# Sheet3.net
KiCad netlist of a schematic drawn in Altium Designer
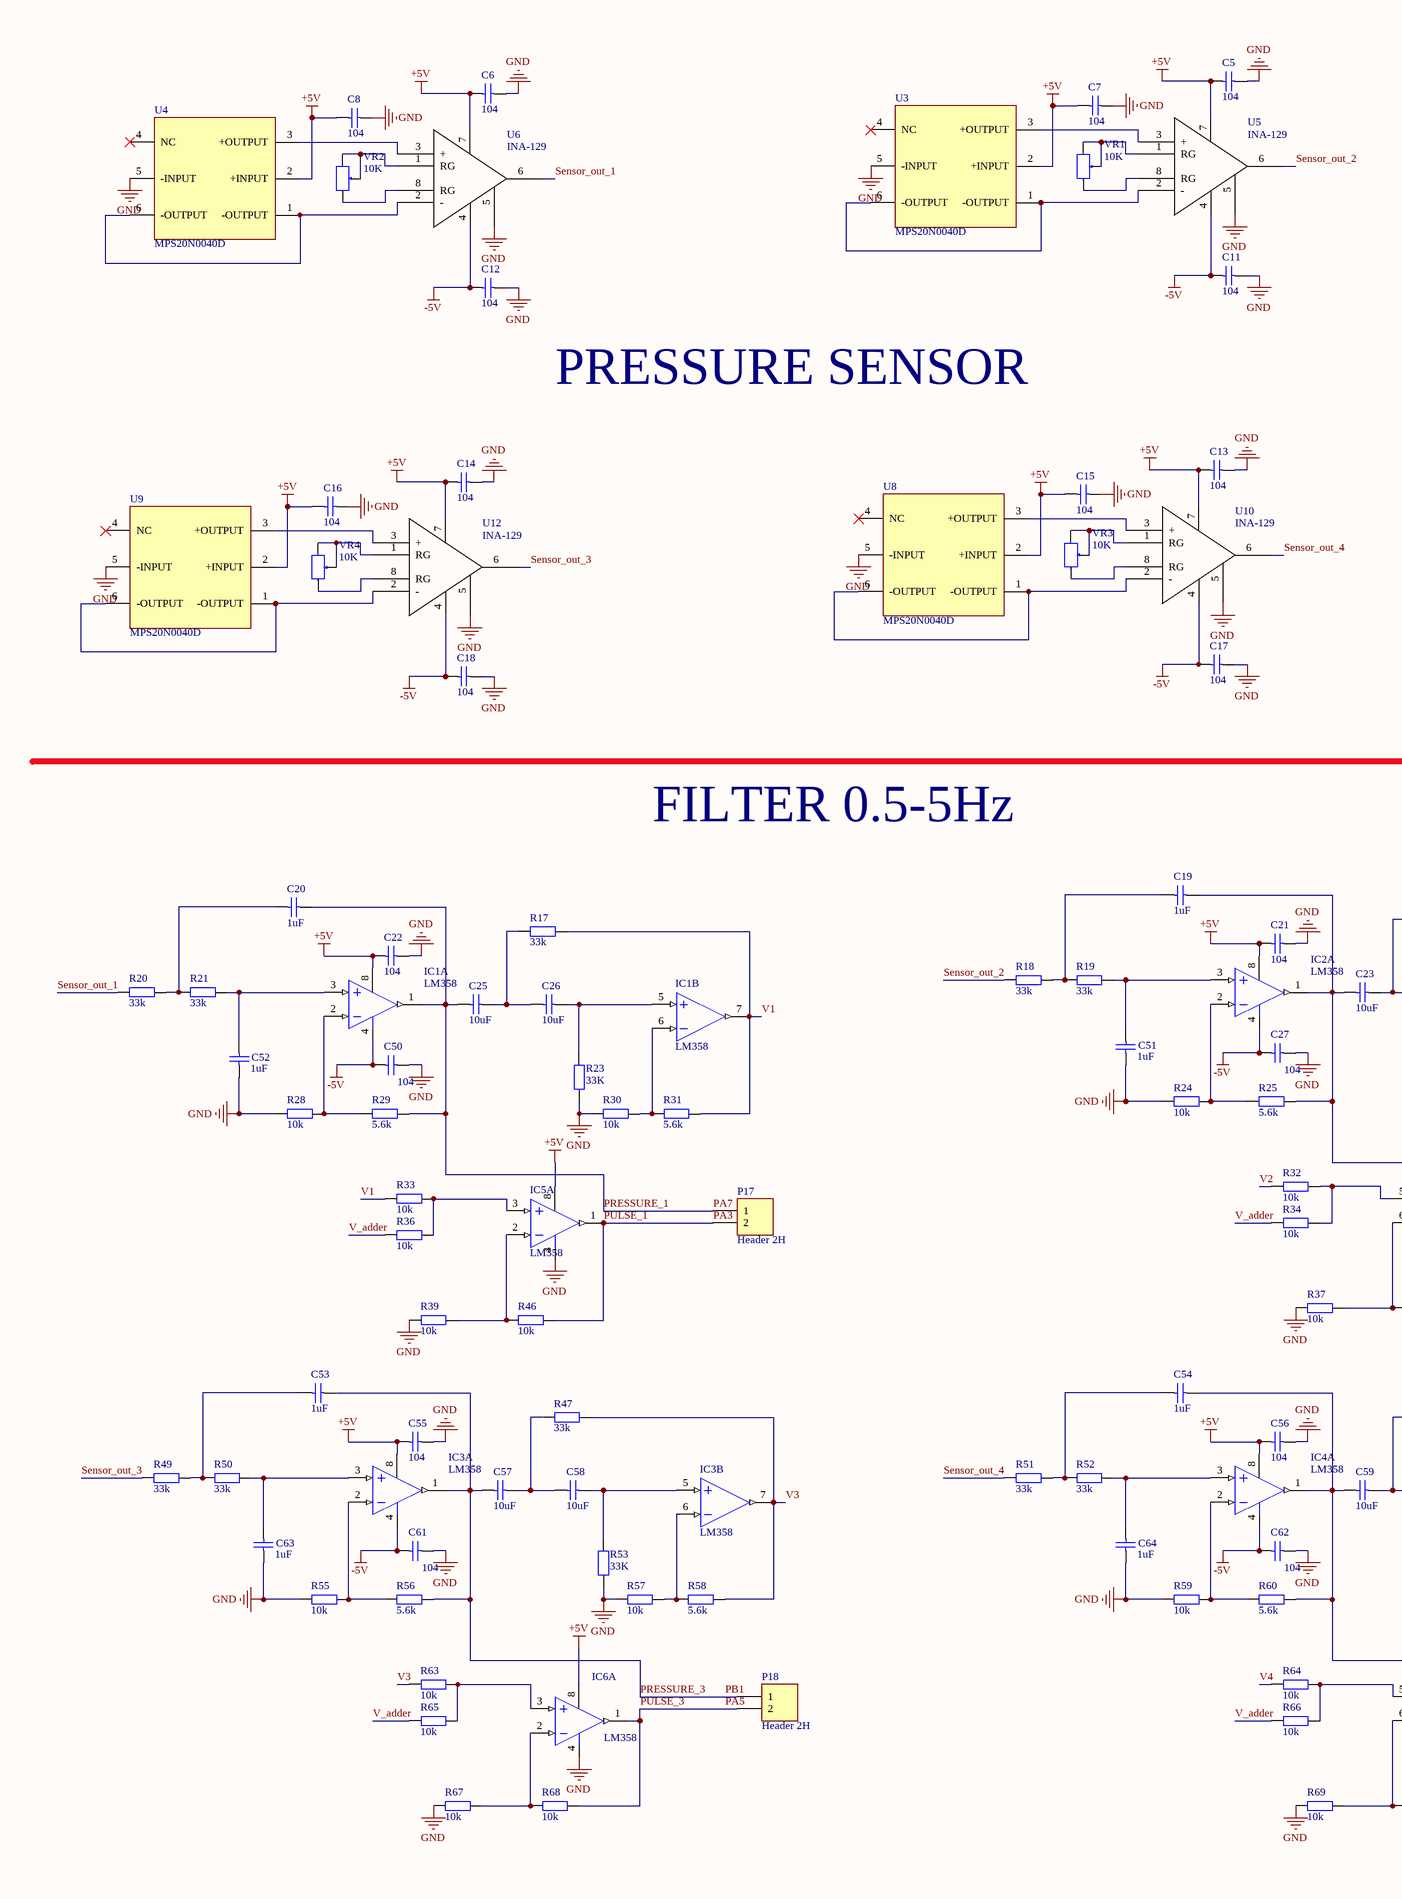
[diagram p0: Sheet3.SchDoc, left]
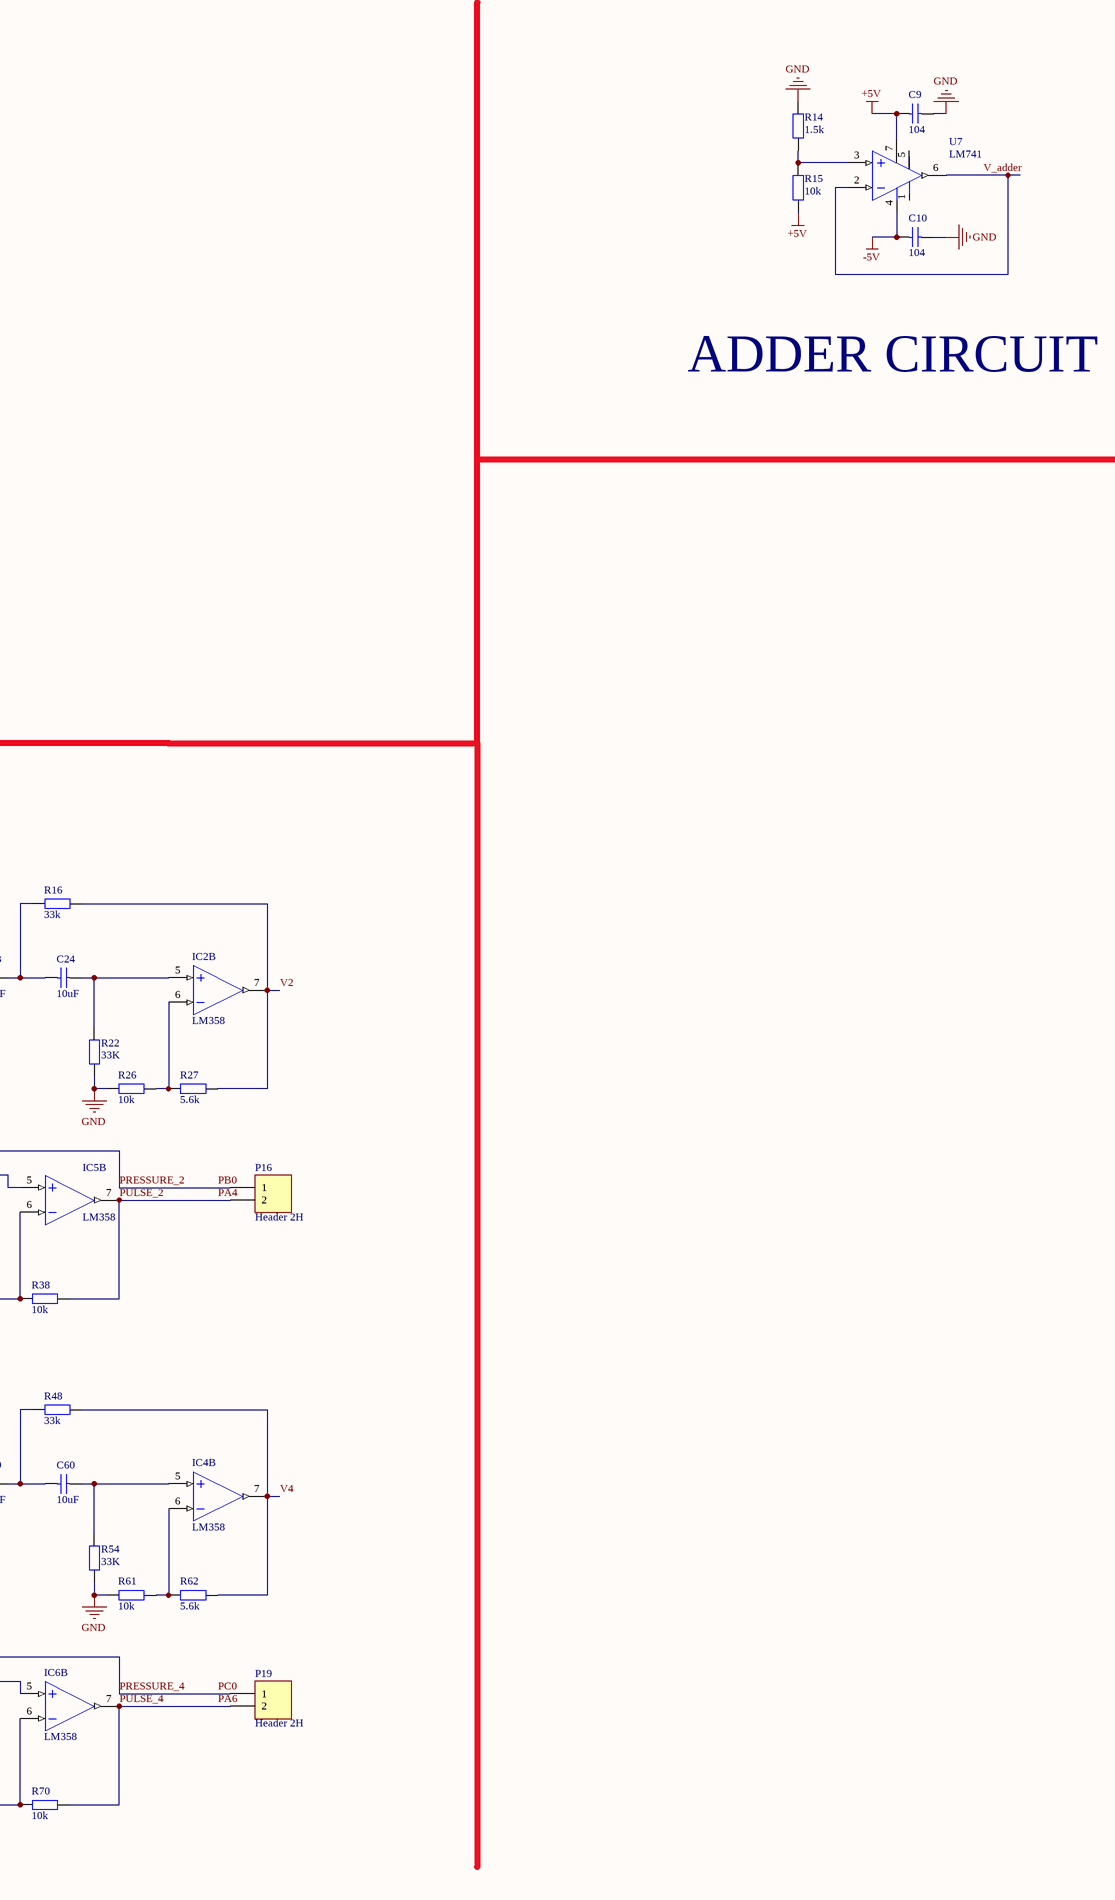
[diagram p1: Sheet3.SchDoc, right]

(export (version "E")
  (design (tool "Eeschema 10.0.6"))
  (components
    (comp (ref "C5")
      (value "104")
      (footprint "0805 CAP")
      (fields (field (name "PUBLISHER") "Altium Limited"))
      (libsource (lib "ThinhNguyenLib") (part "CAP CERAMIC"))
    )
    (comp (ref "C6")
      (value "104")
      (footprint "0805 CAP")
      (fields (field (name "PUBLISHER") "Altium Limited"))
      (libsource (lib "ThinhNguyenLib") (part "CAP CERAMIC"))
    )
    (comp (ref "C7")
      (value "104")
      (footprint "0805 CAP")
      (fields (field (name "PUBLISHER") "Altium Limited"))
      (libsource (lib "ThinhNguyenLib") (part "CAP CERAMIC"))
    )
    (comp (ref "C8")
      (value "104")
      (footprint "0805 CAP")
      (fields (field (name "PUBLISHER") "Altium Limited"))
      (libsource (lib "ThinhNguyenLib") (part "CAP CERAMIC"))
    )
    (comp (ref "C9")
      (value "104")
      (footprint "0805 CAP")
      (fields (field (name "PUBLISHER") "Altium Limited"))
      (libsource (lib "ThinhNguyenLib") (part "CAP CERAMIC"))
    )
    (comp (ref "C10")
      (value "104")
      (footprint "0805 CAP")
      (fields (field (name "PUBLISHER") "Altium Limited"))
      (libsource (lib "ThinhNguyenLib") (part "CAP CERAMIC"))
    )
    (comp (ref "C11")
      (value "104")
      (footprint "0805 CAP")
      (fields (field (name "PUBLISHER") "Altium Limited"))
      (libsource (lib "ThinhNguyenLib") (part "CAP CERAMIC"))
    )
    (comp (ref "C12")
      (value "104")
      (footprint "0805 CAP")
      (fields (field (name "PUBLISHER") "Altium Limited"))
      (libsource (lib "ThinhNguyenLib") (part "CAP CERAMIC"))
    )
    (comp (ref "C13")
      (value "104")
      (footprint "0805 CAP")
      (fields (field (name "PUBLISHER") "Altium Limited"))
      (libsource (lib "ThinhNguyenLib") (part "CAP CERAMIC"))
    )
    (comp (ref "C14")
      (value "104")
      (footprint "0805 CAP")
      (fields (field (name "PUBLISHER") "Altium Limited"))
      (libsource (lib "ThinhNguyenLib") (part "CAP CERAMIC"))
    )
    (comp (ref "C15")
      (value "104")
      (footprint "0805 CAP")
      (fields (field (name "PUBLISHER") "Altium Limited"))
      (libsource (lib "ThinhNguyenLib") (part "CAP CERAMIC"))
    )
    (comp (ref "C16")
      (value "104")
      (footprint "0805 CAP")
      (fields (field (name "PUBLISHER") "Altium Limited"))
      (libsource (lib "ThinhNguyenLib") (part "CAP CERAMIC"))
    )
    (comp (ref "C17")
      (value "104")
      (footprint "0805 CAP")
      (fields (field (name "PUBLISHER") "Altium Limited"))
      (libsource (lib "ThinhNguyenLib") (part "CAP CERAMIC"))
    )
    (comp (ref "C18")
      (value "104")
      (footprint "0805 CAP")
      (fields (field (name "PUBLISHER") "Altium Limited"))
      (libsource (lib "ThinhNguyenLib") (part "CAP CERAMIC"))
    )
    (comp (ref "C19")
      (value "1uF")
      (footprint "0805 CAP")
      (fields (field (name "PUBLISHER") "Altium Limited"))
      (libsource (lib "ThinhNguyenLib") (part "CAP CERAMIC"))
    )
    (comp (ref "C20")
      (value "1uF")
      (footprint "0805 CAP")
      (fields (field (name "PUBLISHER") "Altium Limited"))
      (libsource (lib "ThinhNguyenLib") (part "CAP CERAMIC"))
    )
    (comp (ref "C21")
      (value "104")
      (footprint "0805 CAP")
      (fields (field (name "PUBLISHER") "Altium Limited"))
      (libsource (lib "ThinhNguyenLib") (part "CAP CERAMIC"))
    )
    (comp (ref "C22")
      (value "104")
      (footprint "0805 CAP")
      (fields (field (name "PUBLISHER") "Altium Limited"))
      (libsource (lib "ThinhNguyenLib") (part "CAP CERAMIC"))
    )
    (comp (ref "C23")
      (value "10uF")
      (footprint "0805 CAP")
      (fields (field (name "PUBLISHER") "Altium Limited"))
      (libsource (lib "ThinhNguyenLib") (part "CAP CERAMIC"))
    )
    (comp (ref "C24")
      (value "10uF")
      (footprint "0805 CAP")
      (fields (field (name "PUBLISHER") "Altium Limited"))
      (libsource (lib "ThinhNguyenLib") (part "CAP CERAMIC"))
    )
    (comp (ref "C25")
      (value "10uF")
      (footprint "0805 CAP")
      (fields (field (name "PUBLISHER") "Altium Limited"))
      (libsource (lib "ThinhNguyenLib") (part "CAP CERAMIC"))
    )
    (comp (ref "C26")
      (value "10uF")
      (footprint "0805 CAP")
      (fields (field (name "PUBLISHER") "Altium Limited"))
      (libsource (lib "ThinhNguyenLib") (part "CAP CERAMIC"))
    )
    (comp (ref "C27")
      (value "104")
      (footprint "0805 CAP")
      (fields (field (name "PUBLISHER") "Altium Limited"))
      (libsource (lib "ThinhNguyenLib") (part "CAP CERAMIC"))
    )
    (comp (ref "C50")
      (value "104")
      (footprint "0805 CAP")
      (fields (field (name "PUBLISHER") "Altium Limited"))
      (libsource (lib "ThinhNguyenLib") (part "CAP CERAMIC"))
    )
    (comp (ref "C51")
      (value "1uF")
      (footprint "0805 CAP")
      (fields (field (name "PUBLISHER") "Altium Limited"))
      (libsource (lib "ThinhNguyenLib") (part "CAP CERAMIC"))
    )
    (comp (ref "C52")
      (value "1uF")
      (footprint "0805 CAP")
      (fields (field (name "PUBLISHER") "Altium Limited"))
      (libsource (lib "ThinhNguyenLib") (part "CAP CERAMIC"))
    )
    (comp (ref "C53")
      (value "1uF")
      (footprint "0805 CAP")
      (fields (field (name "PUBLISHER") "Altium Limited"))
      (libsource (lib "ThinhNguyenLib") (part "CAP CERAMIC"))
    )
    (comp (ref "C54")
      (value "1uF")
      (footprint "0805 CAP")
      (fields (field (name "PUBLISHER") "Altium Limited"))
      (libsource (lib "ThinhNguyenLib") (part "CAP CERAMIC"))
    )
    (comp (ref "C55")
      (value "104")
      (footprint "0805 CAP")
      (fields (field (name "PUBLISHER") "Altium Limited"))
      (libsource (lib "ThinhNguyenLib") (part "CAP CERAMIC"))
    )
    (comp (ref "C56")
      (value "104")
      (footprint "0805 CAP")
      (fields (field (name "PUBLISHER") "Altium Limited"))
      (libsource (lib "ThinhNguyenLib") (part "CAP CERAMIC"))
    )
    (comp (ref "C57")
      (value "10uF")
      (footprint "0805 CAP")
      (fields (field (name "PUBLISHER") "Altium Limited"))
      (libsource (lib "ThinhNguyenLib") (part "CAP CERAMIC"))
    )
    (comp (ref "C58")
      (value "10uF")
      (footprint "0805 CAP")
      (fields (field (name "PUBLISHER") "Altium Limited"))
      (libsource (lib "ThinhNguyenLib") (part "CAP CERAMIC"))
    )
    (comp (ref "C59")
      (value "10uF")
      (footprint "0805 CAP")
      (fields (field (name "PUBLISHER") "Altium Limited"))
      (libsource (lib "ThinhNguyenLib") (part "CAP CERAMIC"))
    )
    (comp (ref "C60")
      (value "10uF")
      (footprint "0805 CAP")
      (fields (field (name "PUBLISHER") "Altium Limited"))
      (libsource (lib "ThinhNguyenLib") (part "CAP CERAMIC"))
    )
    (comp (ref "C61")
      (value "104")
      (footprint "0805 CAP")
      (fields (field (name "PUBLISHER") "Altium Limited"))
      (libsource (lib "ThinhNguyenLib") (part "CAP CERAMIC"))
    )
    (comp (ref "C62")
      (value "104")
      (footprint "0805 CAP")
      (fields (field (name "PUBLISHER") "Altium Limited"))
      (libsource (lib "ThinhNguyenLib") (part "CAP CERAMIC"))
    )
    (comp (ref "C63")
      (value "1uF")
      (footprint "0805 CAP")
      (fields (field (name "PUBLISHER") "Altium Limited"))
      (libsource (lib "ThinhNguyenLib") (part "CAP CERAMIC"))
    )
    (comp (ref "C64")
      (value "1uF")
      (footprint "0805 CAP")
      (fields (field (name "PUBLISHER") "Altium Limited"))
      (libsource (lib "ThinhNguyenLib") (part "CAP CERAMIC"))
    )
    (comp (ref "IC1")
      (value "LM358")
      (footprint "SOIC 8PIN")
      (description "Low-Power Dual Operational Amplifier")
      (libsource (lib "syhaunguyen") (part "LM358"))
    )
    (comp (ref "IC2")
      (value "LM358")
      (footprint "SOIC 8PIN")
      (description "Low-Power Dual Operational Amplifier")
      (libsource (lib "syhaunguyen") (part "LM358"))
    )
    (comp (ref "IC3")
      (value "LM358")
      (footprint "SOIC 8PIN")
      (description "Low-Power Dual Operational Amplifier")
      (libsource (lib "syhaunguyen") (part "LM358"))
    )
    (comp (ref "IC4")
      (value "LM358")
      (footprint "SOIC 8PIN")
      (description "Low-Power Dual Operational Amplifier")
      (libsource (lib "syhaunguyen") (part "LM358"))
    )
    (comp (ref "IC5")
      (value "LM358")
      (footprint "SOIC 8PIN")
      (description "Low-Power Dual Operational Amplifier")
      (libsource (lib "syhaunguyen") (part "LM358"))
    )
    (comp (ref "IC6")
      (value "LM358")
      (footprint "SOIC 8PIN")
      (description "Low-Power Dual Operational Amplifier")
      (libsource (lib "syhaunguyen") (part "LM358"))
    )
    (comp (ref "P16")
      (value "Header 2H")
      (footprint "HDR1X2")
      (fields (field (name "PUBLISHER") "Altium Limited"))
      (libsource (lib "ThinhNguyenLib") (part "Header 2H"))
    )
    (comp (ref "P17")
      (value "Header 2H")
      (footprint "HDR1X2")
      (fields (field (name "PUBLISHER") "Altium Limited"))
      (libsource (lib "ThinhNguyenLib") (part "Header 2H"))
    )
    (comp (ref "P18")
      (value "Header 2H")
      (footprint "HDR1X2")
      (fields (field (name "PUBLISHER") "Altium Limited"))
      (libsource (lib "ThinhNguyenLib") (part "Header 2H"))
    )
    (comp (ref "P19")
      (value "Header 2H")
      (footprint "HDR1X2")
      (fields (field (name "PUBLISHER") "Altium Limited"))
      (libsource (lib "ThinhNguyenLib") (part "Header 2H"))
    )
    (comp (ref "R14")
      (value "1.5k")
      (footprint "0805 RESISTOR")
      (libsource (lib "ThinhNguyenLib") (part "RESISTOR"))
    )
    (comp (ref "R15")
      (value "10k")
      (footprint "0805 RESISTOR")
      (libsource (lib "ThinhNguyenLib") (part "RESISTOR"))
    )
    (comp (ref "R16")
      (value "33k")
      (footprint "0805 RESISTOR")
      (libsource (lib "ThinhNguyenLib") (part "RESISTOR"))
    )
    (comp (ref "R17")
      (value "33k")
      (footprint "0805 RESISTOR")
      (libsource (lib "ThinhNguyenLib") (part "RESISTOR"))
    )
    (comp (ref "R18")
      (value "33k")
      (footprint "0805 RESISTOR")
      (libsource (lib "ThinhNguyenLib") (part "RESISTOR"))
    )
    (comp (ref "R19")
      (value "33k")
      (footprint "0805 RESISTOR")
      (libsource (lib "ThinhNguyenLib") (part "RESISTOR"))
    )
    (comp (ref "R20")
      (value "33k")
      (footprint "0805 RESISTOR")
      (libsource (lib "ThinhNguyenLib") (part "RESISTOR"))
    )
    (comp (ref "R21")
      (value "33k")
      (footprint "0805 RESISTOR")
      (libsource (lib "ThinhNguyenLib") (part "RESISTOR"))
    )
    (comp (ref "R22")
      (value "33K")
      (footprint "0805 RESISTOR")
      (libsource (lib "ThinhNguyenLib") (part "RESISTOR"))
    )
    (comp (ref "R23")
      (value "33K")
      (footprint "0805 RESISTOR")
      (libsource (lib "ThinhNguyenLib") (part "RESISTOR"))
    )
    (comp (ref "R24")
      (value "10k")
      (footprint "0805 RESISTOR")
      (libsource (lib "ThinhNguyenLib") (part "RESISTOR"))
    )
    (comp (ref "R25")
      (value "5.6k")
      (footprint "0805 RESISTOR")
      (libsource (lib "ThinhNguyenLib") (part "RESISTOR"))
    )
    (comp (ref "R26")
      (value "10k")
      (footprint "0805 RESISTOR")
      (libsource (lib "ThinhNguyenLib") (part "RESISTOR"))
    )
    (comp (ref "R27")
      (value "5.6k")
      (footprint "0805 RESISTOR")
      (libsource (lib "ThinhNguyenLib") (part "RESISTOR"))
    )
    (comp (ref "R28")
      (value "10k")
      (footprint "0805 RESISTOR")
      (libsource (lib "ThinhNguyenLib") (part "RESISTOR"))
    )
    (comp (ref "R29")
      (value "5.6k")
      (footprint "0805 RESISTOR")
      (libsource (lib "ThinhNguyenLib") (part "RESISTOR"))
    )
    (comp (ref "R30")
      (value "10k")
      (footprint "0805 RESISTOR")
      (libsource (lib "ThinhNguyenLib") (part "RESISTOR"))
    )
    (comp (ref "R31")
      (value "5.6k")
      (footprint "0805 RESISTOR")
      (libsource (lib "ThinhNguyenLib") (part "RESISTOR"))
    )
    (comp (ref "R32")
      (value "10k")
      (footprint "0805 RESISTOR")
      (libsource (lib "ThinhNguyenLib") (part "RESISTOR"))
    )
    (comp (ref "R33")
      (value "10k")
      (footprint "0805 RESISTOR")
      (libsource (lib "ThinhNguyenLib") (part "RESISTOR"))
    )
    (comp (ref "R34")
      (value "10k")
      (footprint "0805 RESISTOR")
      (libsource (lib "ThinhNguyenLib") (part "RESISTOR"))
    )
    (comp (ref "R36")
      (value "10k")
      (footprint "0805 RESISTOR")
      (libsource (lib "ThinhNguyenLib") (part "RESISTOR"))
    )
    (comp (ref "R37")
      (value "10k")
      (footprint "0805 RESISTOR")
      (libsource (lib "ThinhNguyenLib") (part "RESISTOR"))
    )
    (comp (ref "R38")
      (value "10k")
      (footprint "0805 RESISTOR")
      (libsource (lib "ThinhNguyenLib") (part "RESISTOR"))
    )
    (comp (ref "R39")
      (value "10k")
      (footprint "0805 RESISTOR")
      (libsource (lib "ThinhNguyenLib") (part "RESISTOR"))
    )
    (comp (ref "R46")
      (value "10k")
      (footprint "0805 RESISTOR")
      (libsource (lib "ThinhNguyenLib") (part "RESISTOR"))
    )
    (comp (ref "R47")
      (value "33k")
      (footprint "0805 RESISTOR")
      (libsource (lib "ThinhNguyenLib") (part "RESISTOR"))
    )
    (comp (ref "R48")
      (value "33k")
      (footprint "0805 RESISTOR")
      (libsource (lib "ThinhNguyenLib") (part "RESISTOR"))
    )
    (comp (ref "R49")
      (value "33k")
      (footprint "0805 RESISTOR")
      (libsource (lib "ThinhNguyenLib") (part "RESISTOR"))
    )
    (comp (ref "R50")
      (value "33k")
      (footprint "0805 RESISTOR")
      (libsource (lib "ThinhNguyenLib") (part "RESISTOR"))
    )
    (comp (ref "R51")
      (value "33k")
      (footprint "0805 RESISTOR")
      (libsource (lib "ThinhNguyenLib") (part "RESISTOR"))
    )
    (comp (ref "R52")
      (value "33k")
      (footprint "0805 RESISTOR")
      (libsource (lib "ThinhNguyenLib") (part "RESISTOR"))
    )
    (comp (ref "R53")
      (value "33K")
      (footprint "0805 RESISTOR")
      (libsource (lib "ThinhNguyenLib") (part "RESISTOR"))
    )
    (comp (ref "R54")
      (value "33K")
      (footprint "0805 RESISTOR")
      (libsource (lib "ThinhNguyenLib") (part "RESISTOR"))
    )
    (comp (ref "R55")
      (value "10k")
      (footprint "0805 RESISTOR")
      (libsource (lib "ThinhNguyenLib") (part "RESISTOR"))
    )
    (comp (ref "R56")
      (value "5.6k")
      (footprint "0805 RESISTOR")
      (libsource (lib "ThinhNguyenLib") (part "RESISTOR"))
    )
    (comp (ref "R57")
      (value "10k")
      (footprint "0805 RESISTOR")
      (libsource (lib "ThinhNguyenLib") (part "RESISTOR"))
    )
    (comp (ref "R58")
      (value "5.6k")
      (footprint "0805 RESISTOR")
      (libsource (lib "ThinhNguyenLib") (part "RESISTOR"))
    )
    (comp (ref "R59")
      (value "10k")
      (footprint "0805 RESISTOR")
      (libsource (lib "ThinhNguyenLib") (part "RESISTOR"))
    )
    (comp (ref "R60")
      (value "5.6k")
      (footprint "0805 RESISTOR")
      (libsource (lib "ThinhNguyenLib") (part "RESISTOR"))
    )
    (comp (ref "R61")
      (value "10k")
      (footprint "0805 RESISTOR")
      (libsource (lib "ThinhNguyenLib") (part "RESISTOR"))
    )
    (comp (ref "R62")
      (value "5.6k")
      (footprint "0805 RESISTOR")
      (libsource (lib "ThinhNguyenLib") (part "RESISTOR"))
    )
    (comp (ref "R63")
      (value "10k")
      (footprint "0805 RESISTOR")
      (libsource (lib "ThinhNguyenLib") (part "RESISTOR"))
    )
    (comp (ref "R64")
      (value "10k")
      (footprint "0805 RESISTOR")
      (libsource (lib "ThinhNguyenLib") (part "RESISTOR"))
    )
    (comp (ref "R65")
      (value "10k")
      (footprint "0805 RESISTOR")
      (libsource (lib "ThinhNguyenLib") (part "RESISTOR"))
    )
    (comp (ref "R66")
      (value "10k")
      (footprint "0805 RESISTOR")
      (libsource (lib "ThinhNguyenLib") (part "RESISTOR"))
    )
    (comp (ref "R67")
      (value "10k")
      (footprint "0805 RESISTOR")
      (libsource (lib "ThinhNguyenLib") (part "RESISTOR"))
    )
    (comp (ref "R68")
      (value "10k")
      (footprint "0805 RESISTOR")
      (libsource (lib "ThinhNguyenLib") (part "RESISTOR"))
    )
    (comp (ref "R69")
      (value "10k")
      (footprint "0805 RESISTOR")
      (libsource (lib "ThinhNguyenLib") (part "RESISTOR"))
    )
    (comp (ref "R70")
      (value "10k")
      (footprint "0805 RESISTOR")
      (libsource (lib "ThinhNguyenLib") (part "RESISTOR"))
    )
    (comp (ref "U3")
      (value "MPS20N0040D")
      (footprint "MPS20N0040D-S")
      (libsource (lib "ThinhNguyenLib") (part "MPS20N0040D"))
    )
    (comp (ref "U4")
      (value "MPS20N0040D")
      (footprint "MPS20N0040D-S")
      (libsource (lib "ThinhNguyenLib") (part "MPS20N0040D"))
    )
    (comp (ref "U5")
      (value "INA-129")
      (footprint "DIP 8")
      (libsource (lib "ThinhNguyenLib") (part "INA-129"))
    )
    (comp (ref "U6")
      (value "INA-129")
      (footprint "DIP 8")
      (libsource (lib "ThinhNguyenLib") (part "INA-129"))
    )
    (comp (ref "U7")
      (value "LM741")
      (footprint "SOIC 8PIN")
      (libsource (lib "ThinhNguyenLib") (part "LM741"))
    )
    (comp (ref "U8")
      (value "MPS20N0040D")
      (footprint "MPS20N0040D-S")
      (libsource (lib "ThinhNguyenLib") (part "MPS20N0040D"))
    )
    (comp (ref "U9")
      (value "MPS20N0040D")
      (footprint "MPS20N0040D-S")
      (libsource (lib "ThinhNguyenLib") (part "MPS20N0040D"))
    )
    (comp (ref "U10")
      (value "INA-129")
      (footprint "DIP 8")
      (libsource (lib "ThinhNguyenLib") (part "INA-129"))
    )
    (comp (ref "U12")
      (value "INA-129")
      (footprint "DIP 8")
      (libsource (lib "ThinhNguyenLib") (part "INA-129"))
    )
    (comp (ref "VR1") (value "10K") (footprint "RVAR") (libsource (lib "ThinhNguyenLib") (part "VAR RES")))
    (comp (ref "VR2") (value "10K") (footprint "RVAR") (libsource (lib "ThinhNguyenLib") (part "VAR RES")))
    (comp (ref "VR3") (value "10K") (footprint "RVAR") (libsource (lib "ThinhNguyenLib") (part "VAR RES")))
    (comp (ref "VR4") (value "10K") (footprint "RVAR") (libsource (lib "ThinhNguyenLib") (part "VAR RES")))
  )
  (nets
    (net (code "1") (name "+5V") (class "Default")
      (node (ref "C13") (pin "1") (pinfunction "1_1") (pintype "passive"))
      (node (ref "C14") (pin "1") (pinfunction "1_1") (pintype "passive"))
      (node (ref "C15") (pin "2") (pinfunction "2_2") (pintype "passive"))
      (node (ref "C16") (pin "2") (pinfunction "2_2") (pintype "passive"))
      (node (ref "C21") (pin "1") (pinfunction "1_1") (pintype "passive"))
      (node (ref "C22") (pin "1") (pinfunction "1_1") (pintype "passive"))
      (node (ref "C5") (pin "1") (pinfunction "1_1") (pintype "passive"))
      (node (ref "C55") (pin "1") (pinfunction "1_1") (pintype "passive"))
      (node (ref "C56") (pin "1") (pinfunction "1_1") (pintype "passive"))
      (node (ref "C6") (pin "1") (pinfunction "1_1") (pintype "passive"))
      (node (ref "C7") (pin "2") (pinfunction "2_2") (pintype "passive"))
      (node (ref "C8") (pin "2") (pinfunction "2_2") (pintype "passive"))
      (node (ref "C9") (pin "1") (pinfunction "1_1") (pintype "passive"))
      (node (ref "IC1") (pin "8") (pinfunction "+V_8") (pintype "passive"))
      (node (ref "IC2") (pin "8") (pinfunction "+V_8") (pintype "passive"))
      (node (ref "IC3") (pin "8") (pinfunction "+V_8") (pintype "passive"))
      (node (ref "IC4") (pin "8") (pinfunction "+V_8") (pintype "passive"))
      (node (ref "IC5") (pin "8") (pinfunction "+V_8") (pintype "passive"))
      (node (ref "IC6") (pin "8") (pinfunction "+V_8") (pintype "passive"))
      (node (ref "R15") (pin "2") (pinfunction "2_2") (pintype "passive"))
      (node (ref "U10") (pin "7") (pintype "passive"))
      (node (ref "U12") (pin "7") (pintype "passive"))
      (node (ref "U3") (pin "2") (pinfunction "+INPUT_2") (pintype "passive"))
      (node (ref "U4") (pin "2") (pinfunction "+INPUT_2") (pintype "passive"))
      (node (ref "U5") (pin "7") (pintype "passive"))
      (node (ref "U6") (pin "7") (pintype "passive"))
      (node (ref "U7") (pin "7") (pinfunction "+V_7") (pintype "passive"))
      (node (ref "U8") (pin "2") (pinfunction "+INPUT_2") (pintype "passive"))
      (node (ref "U9") (pin "2") (pinfunction "+INPUT_2") (pintype "passive"))
    )
    (net (code "2") (name "-5V") (class "Default")
      (node (ref "C10") (pin "1") (pinfunction "1_1") (pintype "passive"))
      (node (ref "C11") (pin "2") (pinfunction "2_2") (pintype "passive"))
      (node (ref "C12") (pin "2") (pinfunction "2_2") (pintype "passive"))
      (node (ref "C17") (pin "2") (pinfunction "2_2") (pintype "passive"))
      (node (ref "C18") (pin "2") (pinfunction "2_2") (pintype "passive"))
      (node (ref "C27") (pin "1") (pinfunction "1_1") (pintype "passive"))
      (node (ref "C50") (pin "1") (pinfunction "1_1") (pintype "passive"))
      (node (ref "C61") (pin "1") (pinfunction "1_1") (pintype "passive"))
      (node (ref "C62") (pin "1") (pinfunction "1_1") (pintype "passive"))
      (node (ref "IC1") (pin "4") (pinfunction "-V_4") (pintype "passive"))
      (node (ref "IC2") (pin "4") (pinfunction "-V_4") (pintype "passive"))
      (node (ref "IC3") (pin "4") (pinfunction "-V_4") (pintype "passive"))
      (node (ref "IC4") (pin "4") (pinfunction "-V_4") (pintype "passive"))
      (node (ref "U10") (pin "4") (pintype "passive"))
      (node (ref "U12") (pin "4") (pintype "passive"))
      (node (ref "U5") (pin "4") (pintype "passive"))
      (node (ref "U6") (pin "4") (pintype "passive"))
      (node (ref "U7") (pin "4") (pinfunction "-V_4") (pintype "passive"))
    )
    (net (code "4") (name "/PA3") (class "Default")
      (node (ref "IC5") (pin "1") (pinfunction "OUT_1") (pintype "output"))
      (node (ref "P17") (pin "2") (pinfunction "2_2") (pintype "passive"))
      (node (ref "R46") (pin "2") (pinfunction "2_2") (pintype "passive"))
    )
    (net (code "5") (name "/PA4") (class "Default")
      (node (ref "IC5") (pin "7") (pinfunction "OUT_7") (pintype "output"))
      (node (ref "P16") (pin "2") (pinfunction "2_2") (pintype "passive"))
      (node (ref "R38") (pin "2") (pinfunction "2_2") (pintype "passive"))
    )
    (net (code "6") (name "/PA5") (class "Default")
      (node (ref "IC6") (pin "1") (pinfunction "OUT_1") (pintype "output"))
      (node (ref "P18") (pin "2") (pinfunction "2_2") (pintype "passive"))
      (node (ref "R68") (pin "2") (pinfunction "2_2") (pintype "passive"))
    )
    (net (code "7") (name "/PA6") (class "Default")
      (node (ref "IC6") (pin "7") (pinfunction "OUT_7") (pintype "output"))
      (node (ref "P19") (pin "2") (pinfunction "2_2") (pintype "passive"))
      (node (ref "R70") (pin "2") (pinfunction "2_2") (pintype "passive"))
    )
    (net (code "8") (name "/PA7") (class "Default")
      (node (ref "C20") (pin "2") (pinfunction "2_2") (pintype "passive"))
      (node (ref "C25") (pin "1") (pinfunction "1_1") (pintype "passive"))
      (node (ref "IC1") (pin "1") (pinfunction "OUT_1") (pintype "output"))
      (node (ref "P17") (pin "1") (pinfunction "1_1") (pintype "passive"))
      (node (ref "R29") (pin "2") (pinfunction "2_2") (pintype "passive"))
    )
    (net (code "9") (name "/PB0") (class "Default")
      (node (ref "C19") (pin "2") (pinfunction "2_2") (pintype "passive"))
      (node (ref "C23") (pin "1") (pinfunction "1_1") (pintype "passive"))
      (node (ref "IC2") (pin "1") (pinfunction "OUT_1") (pintype "output"))
      (node (ref "P16") (pin "1") (pinfunction "1_1") (pintype "passive"))
      (node (ref "R25") (pin "2") (pinfunction "2_2") (pintype "passive"))
    )
    (net (code "10") (name "/PB1") (class "Default")
      (node (ref "C53") (pin "2") (pinfunction "2_2") (pintype "passive"))
      (node (ref "C57") (pin "1") (pinfunction "1_1") (pintype "passive"))
      (node (ref "IC3") (pin "1") (pinfunction "OUT_1") (pintype "output"))
      (node (ref "P18") (pin "1") (pinfunction "1_1") (pintype "passive"))
      (node (ref "R56") (pin "2") (pinfunction "2_2") (pintype "passive"))
    )
    (net (code "11") (name "/PC0") (class "Default")
      (node (ref "C54") (pin "2") (pinfunction "2_2") (pintype "passive"))
      (node (ref "C59") (pin "1") (pinfunction "1_1") (pintype "passive"))
      (node (ref "IC4") (pin "1") (pinfunction "OUT_1") (pintype "output"))
      (node (ref "P19") (pin "1") (pinfunction "1_1") (pintype "passive"))
      (node (ref "R60") (pin "2") (pinfunction "2_2") (pintype "passive"))
    )
    (net (code "12") (name "/Sensor_out_1") (class "Default")
      (node (ref "R20") (pin "1") (pinfunction "1_1") (pintype "passive"))
      (node (ref "U6") (pin "6") (pintype "passive"))
    )
    (net (code "13") (name "/Sensor_out_2") (class "Default")
      (node (ref "R18") (pin "1") (pinfunction "1_1") (pintype "passive"))
      (node (ref "U5") (pin "6") (pintype "passive"))
    )
    (net (code "14") (name "/Sensor_out_3") (class "Default")
      (node (ref "R49") (pin "1") (pinfunction "1_1") (pintype "passive"))
      (node (ref "U12") (pin "6") (pintype "passive"))
    )
    (net (code "15") (name "/Sensor_out_4") (class "Default")
      (node (ref "R51") (pin "1") (pinfunction "1_1") (pintype "passive"))
      (node (ref "U10") (pin "6") (pintype "passive"))
    )
    (net (code "16") (name "/V1") (class "Default")
      (node (ref "IC1") (pin "7") (pinfunction "OUT_7") (pintype "output"))
      (node (ref "R17") (pin "2") (pinfunction "2_2") (pintype "passive"))
      (node (ref "R31") (pin "2") (pinfunction "2_2") (pintype "passive"))
      (node (ref "R33") (pin "1") (pinfunction "1_1") (pintype "passive"))
    )
    (net (code "17") (name "/V2") (class "Default")
      (node (ref "IC2") (pin "7") (pinfunction "OUT_7") (pintype "output"))
      (node (ref "R16") (pin "2") (pinfunction "2_2") (pintype "passive"))
      (node (ref "R27") (pin "2") (pinfunction "2_2") (pintype "passive"))
      (node (ref "R32") (pin "1") (pinfunction "1_1") (pintype "passive"))
    )
    (net (code "18") (name "/V3") (class "Default")
      (node (ref "IC3") (pin "7") (pinfunction "OUT_7") (pintype "output"))
      (node (ref "R47") (pin "2") (pinfunction "2_2") (pintype "passive"))
      (node (ref "R58") (pin "2") (pinfunction "2_2") (pintype "passive"))
      (node (ref "R63") (pin "1") (pinfunction "1_1") (pintype "passive"))
    )
    (net (code "19") (name "/V4") (class "Default")
      (node (ref "IC4") (pin "7") (pinfunction "OUT_7") (pintype "output"))
      (node (ref "R48") (pin "2") (pinfunction "2_2") (pintype "passive"))
      (node (ref "R62") (pin "2") (pinfunction "2_2") (pintype "passive"))
      (node (ref "R64") (pin "1") (pinfunction "1_1") (pintype "passive"))
    )
    (net (code "20") (name "/V_adder") (class "Default")
      (node (ref "R34") (pin "1") (pinfunction "1_1") (pintype "passive"))
      (node (ref "R36") (pin "1") (pinfunction "1_1") (pintype "passive"))
      (node (ref "R65") (pin "1") (pinfunction "1_1") (pintype "passive"))
      (node (ref "R66") (pin "1") (pinfunction "1_1") (pintype "passive"))
      (node (ref "U7") (pin "2") (pinfunction "IN-_2") (pintype "input"))
      (node (ref "U7") (pin "6") (pinfunction "OUT_6") (pintype "output"))
    )
    (net (code "21") (name "GND") (class "Default")
      (node (ref "C10") (pin "2") (pinfunction "2_2") (pintype "passive"))
      (node (ref "C11") (pin "1") (pinfunction "1_1") (pintype "passive"))
      (node (ref "C12") (pin "1") (pinfunction "1_1") (pintype "passive"))
      (node (ref "C13") (pin "2") (pinfunction "2_2") (pintype "passive"))
      (node (ref "C14") (pin "2") (pinfunction "2_2") (pintype "passive"))
      (node (ref "C15") (pin "1") (pinfunction "1_1") (pintype "passive"))
      (node (ref "C16") (pin "1") (pinfunction "1_1") (pintype "passive"))
      (node (ref "C17") (pin "1") (pinfunction "1_1") (pintype "passive"))
      (node (ref "C18") (pin "1") (pinfunction "1_1") (pintype "passive"))
      (node (ref "C21") (pin "2") (pinfunction "2_2") (pintype "passive"))
      (node (ref "C22") (pin "2") (pinfunction "2_2") (pintype "passive"))
      (node (ref "C27") (pin "2") (pinfunction "2_2") (pintype "passive"))
      (node (ref "C5") (pin "2") (pinfunction "2_2") (pintype "passive"))
      (node (ref "C50") (pin "2") (pinfunction "2_2") (pintype "passive"))
      (node (ref "C51") (pin "2") (pinfunction "2_2") (pintype "passive"))
      (node (ref "C52") (pin "2") (pinfunction "2_2") (pintype "passive"))
      (node (ref "C55") (pin "2") (pinfunction "2_2") (pintype "passive"))
      (node (ref "C56") (pin "2") (pinfunction "2_2") (pintype "passive"))
      (node (ref "C6") (pin "2") (pinfunction "2_2") (pintype "passive"))
      (node (ref "C61") (pin "2") (pinfunction "2_2") (pintype "passive"))
      (node (ref "C62") (pin "2") (pinfunction "2_2") (pintype "passive"))
      (node (ref "C63") (pin "2") (pinfunction "2_2") (pintype "passive"))
      (node (ref "C64") (pin "2") (pinfunction "2_2") (pintype "passive"))
      (node (ref "C7") (pin "1") (pinfunction "1_1") (pintype "passive"))
      (node (ref "C8") (pin "1") (pinfunction "1_1") (pintype "passive"))
      (node (ref "C9") (pin "2") (pinfunction "2_2") (pintype "passive"))
      (node (ref "IC5") (pin "4") (pinfunction "-V_4") (pintype "passive"))
      (node (ref "IC6") (pin "4") (pinfunction "-V_4") (pintype "passive"))
      (node (ref "R14") (pin "1") (pinfunction "1_1") (pintype "passive"))
      (node (ref "R22") (pin "1") (pinfunction "1_1") (pintype "passive"))
      (node (ref "R23") (pin "1") (pinfunction "1_1") (pintype "passive"))
      (node (ref "R24") (pin "1") (pinfunction "1_1") (pintype "passive"))
      (node (ref "R26") (pin "1") (pinfunction "1_1") (pintype "passive"))
      (node (ref "R28") (pin "1") (pinfunction "1_1") (pintype "passive"))
      (node (ref "R30") (pin "1") (pinfunction "1_1") (pintype "passive"))
      (node (ref "R37") (pin "1") (pinfunction "1_1") (pintype "passive"))
      (node (ref "R39") (pin "1") (pinfunction "1_1") (pintype "passive"))
      (node (ref "R53") (pin "1") (pinfunction "1_1") (pintype "passive"))
      (node (ref "R54") (pin "1") (pinfunction "1_1") (pintype "passive"))
      (node (ref "R55") (pin "1") (pinfunction "1_1") (pintype "passive"))
      (node (ref "R57") (pin "1") (pinfunction "1_1") (pintype "passive"))
      (node (ref "R59") (pin "1") (pinfunction "1_1") (pintype "passive"))
      (node (ref "R61") (pin "1") (pinfunction "1_1") (pintype "passive"))
      (node (ref "R67") (pin "1") (pinfunction "1_1") (pintype "passive"))
      (node (ref "R69") (pin "1") (pinfunction "1_1") (pintype "passive"))
      (node (ref "U10") (pin "5") (pintype "passive"))
      (node (ref "U12") (pin "5") (pintype "passive"))
      (node (ref "U3") (pin "5") (pinfunction "-INPUT_5") (pintype "passive"))
      (node (ref "U4") (pin "5") (pinfunction "-INPUT_5") (pintype "passive"))
      (node (ref "U5") (pin "5") (pintype "passive"))
      (node (ref "U6") (pin "5") (pintype "passive"))
      (node (ref "U8") (pin "5") (pinfunction "-INPUT_5") (pintype "passive"))
      (node (ref "U9") (pin "5") (pinfunction "-INPUT_5") (pintype "passive"))
    )
    (net (code "22") (name "Net-(C19-Pad1)") (class "Default")
      (node (ref "C19") (pin "1") (pinfunction "1_1") (pintype "passive"))
      (node (ref "R18") (pin "2") (pinfunction "2_2") (pintype "passive"))
      (node (ref "R19") (pin "1") (pinfunction "1_1") (pintype "passive"))
    )
    (net (code "23") (name "Net-(C20-Pad1)") (class "Default")
      (node (ref "C20") (pin "1") (pinfunction "1_1") (pintype "passive"))
      (node (ref "R20") (pin "2") (pinfunction "2_2") (pintype "passive"))
      (node (ref "R21") (pin "1") (pinfunction "1_1") (pintype "passive"))
    )
    (net (code "24") (name "Net-(C23-Pad2)") (class "Default")
      (node (ref "C23") (pin "2") (pinfunction "2_2") (pintype "passive"))
      (node (ref "C24") (pin "1") (pinfunction "1_1") (pintype "passive"))
      (node (ref "R16") (pin "1") (pinfunction "1_1") (pintype "passive"))
    )
    (net (code "25") (name "Net-(C25-Pad2)") (class "Default")
      (node (ref "C25") (pin "2") (pinfunction "2_2") (pintype "passive"))
      (node (ref "C26") (pin "1") (pinfunction "1_1") (pintype "passive"))
      (node (ref "R17") (pin "1") (pinfunction "1_1") (pintype "passive"))
    )
    (net (code "26") (name "Net-(C53-Pad1)") (class "Default")
      (node (ref "C53") (pin "1") (pinfunction "1_1") (pintype "passive"))
      (node (ref "R49") (pin "2") (pinfunction "2_2") (pintype "passive"))
      (node (ref "R50") (pin "1") (pinfunction "1_1") (pintype "passive"))
    )
    (net (code "27") (name "Net-(C54-Pad1)") (class "Default")
      (node (ref "C54") (pin "1") (pinfunction "1_1") (pintype "passive"))
      (node (ref "R51") (pin "2") (pinfunction "2_2") (pintype "passive"))
      (node (ref "R52") (pin "1") (pinfunction "1_1") (pintype "passive"))
    )
    (net (code "28") (name "Net-(C57-Pad2)") (class "Default")
      (node (ref "C57") (pin "2") (pinfunction "2_2") (pintype "passive"))
      (node (ref "C58") (pin "1") (pinfunction "1_1") (pintype "passive"))
      (node (ref "R47") (pin "1") (pinfunction "1_1") (pintype "passive"))
    )
    (net (code "29") (name "Net-(C59-Pad2)") (class "Default")
      (node (ref "C59") (pin "2") (pinfunction "2_2") (pintype "passive"))
      (node (ref "C60") (pin "1") (pinfunction "1_1") (pintype "passive"))
      (node (ref "R48") (pin "1") (pinfunction "1_1") (pintype "passive"))
    )
    (net (code "30") (name "Net-(IC1A-IN+)") (class "Default")
      (node (ref "C52") (pin "1") (pinfunction "1_1") (pintype "passive"))
      (node (ref "IC1") (pin "3") (pinfunction "IN+_3") (pintype "input"))
      (node (ref "R21") (pin "2") (pinfunction "2_2") (pintype "passive"))
    )
    (net (code "31") (name "Net-(IC1A-IN-)") (class "Default")
      (node (ref "IC1") (pin "2") (pinfunction "IN-_2") (pintype "input"))
      (node (ref "R28") (pin "2") (pinfunction "2_2") (pintype "passive"))
      (node (ref "R29") (pin "1") (pinfunction "1_1") (pintype "passive"))
    )
    (net (code "32") (name "Net-(IC1B-IN+)") (class "Default")
      (node (ref "C26") (pin "2") (pinfunction "2_2") (pintype "passive"))
      (node (ref "IC1") (pin "5") (pinfunction "IN+_5") (pintype "input"))
      (node (ref "R23") (pin "2") (pinfunction "2_2") (pintype "passive"))
    )
    (net (code "33") (name "Net-(IC1B-IN-)") (class "Default")
      (node (ref "IC1") (pin "6") (pinfunction "IN-_6") (pintype "input"))
      (node (ref "R30") (pin "2") (pinfunction "2_2") (pintype "passive"))
      (node (ref "R31") (pin "1") (pinfunction "1_1") (pintype "passive"))
    )
    (net (code "34") (name "Net-(IC2A-IN+)") (class "Default")
      (node (ref "C51") (pin "1") (pinfunction "1_1") (pintype "passive"))
      (node (ref "IC2") (pin "3") (pinfunction "IN+_3") (pintype "input"))
      (node (ref "R19") (pin "2") (pinfunction "2_2") (pintype "passive"))
    )
    (net (code "35") (name "Net-(IC2A-IN-)") (class "Default")
      (node (ref "IC2") (pin "2") (pinfunction "IN-_2") (pintype "input"))
      (node (ref "R24") (pin "2") (pinfunction "2_2") (pintype "passive"))
      (node (ref "R25") (pin "1") (pinfunction "1_1") (pintype "passive"))
    )
    (net (code "36") (name "Net-(IC2B-IN+)") (class "Default")
      (node (ref "C24") (pin "2") (pinfunction "2_2") (pintype "passive"))
      (node (ref "IC2") (pin "5") (pinfunction "IN+_5") (pintype "input"))
      (node (ref "R22") (pin "2") (pinfunction "2_2") (pintype "passive"))
    )
    (net (code "37") (name "Net-(IC2B-IN-)") (class "Default")
      (node (ref "IC2") (pin "6") (pinfunction "IN-_6") (pintype "input"))
      (node (ref "R26") (pin "2") (pinfunction "2_2") (pintype "passive"))
      (node (ref "R27") (pin "1") (pinfunction "1_1") (pintype "passive"))
    )
    (net (code "38") (name "Net-(IC3A-IN+)") (class "Default")
      (node (ref "C63") (pin "1") (pinfunction "1_1") (pintype "passive"))
      (node (ref "IC3") (pin "3") (pinfunction "IN+_3") (pintype "input"))
      (node (ref "R50") (pin "2") (pinfunction "2_2") (pintype "passive"))
    )
    (net (code "39") (name "Net-(IC3A-IN-)") (class "Default")
      (node (ref "IC3") (pin "2") (pinfunction "IN-_2") (pintype "input"))
      (node (ref "R55") (pin "2") (pinfunction "2_2") (pintype "passive"))
      (node (ref "R56") (pin "1") (pinfunction "1_1") (pintype "passive"))
    )
    (net (code "40") (name "Net-(IC3B-IN+)") (class "Default")
      (node (ref "C58") (pin "2") (pinfunction "2_2") (pintype "passive"))
      (node (ref "IC3") (pin "5") (pinfunction "IN+_5") (pintype "input"))
      (node (ref "R53") (pin "2") (pinfunction "2_2") (pintype "passive"))
    )
    (net (code "41") (name "Net-(IC3B-IN-)") (class "Default")
      (node (ref "IC3") (pin "6") (pinfunction "IN-_6") (pintype "input"))
      (node (ref "R57") (pin "2") (pinfunction "2_2") (pintype "passive"))
      (node (ref "R58") (pin "1") (pinfunction "1_1") (pintype "passive"))
    )
    (net (code "42") (name "Net-(IC4A-IN+)") (class "Default")
      (node (ref "C64") (pin "1") (pinfunction "1_1") (pintype "passive"))
      (node (ref "IC4") (pin "3") (pinfunction "IN+_3") (pintype "input"))
      (node (ref "R52") (pin "2") (pinfunction "2_2") (pintype "passive"))
    )
    (net (code "43") (name "Net-(IC4A-IN-)") (class "Default")
      (node (ref "IC4") (pin "2") (pinfunction "IN-_2") (pintype "input"))
      (node (ref "R59") (pin "2") (pinfunction "2_2") (pintype "passive"))
      (node (ref "R60") (pin "1") (pinfunction "1_1") (pintype "passive"))
    )
    (net (code "44") (name "Net-(IC4B-IN+)") (class "Default")
      (node (ref "C60") (pin "2") (pinfunction "2_2") (pintype "passive"))
      (node (ref "IC4") (pin "5") (pinfunction "IN+_5") (pintype "input"))
      (node (ref "R54") (pin "2") (pinfunction "2_2") (pintype "passive"))
    )
    (net (code "45") (name "Net-(IC4B-IN-)") (class "Default")
      (node (ref "IC4") (pin "6") (pinfunction "IN-_6") (pintype "input"))
      (node (ref "R61") (pin "2") (pinfunction "2_2") (pintype "passive"))
      (node (ref "R62") (pin "1") (pinfunction "1_1") (pintype "passive"))
    )
    (net (code "46") (name "Net-(IC5A-IN+)") (class "Default")
      (node (ref "IC5") (pin "3") (pinfunction "IN+_3") (pintype "input"))
      (node (ref "R33") (pin "2") (pinfunction "2_2") (pintype "passive"))
      (node (ref "R36") (pin "2") (pinfunction "2_2") (pintype "passive"))
    )
    (net (code "47") (name "Net-(IC5A-IN-)") (class "Default")
      (node (ref "IC5") (pin "2") (pinfunction "IN-_2") (pintype "input"))
      (node (ref "R39") (pin "2") (pinfunction "2_2") (pintype "passive"))
      (node (ref "R46") (pin "1") (pinfunction "1_1") (pintype "passive"))
    )
    (net (code "48") (name "Net-(IC5B-IN+)") (class "Default")
      (node (ref "IC5") (pin "5") (pinfunction "IN+_5") (pintype "input"))
      (node (ref "R32") (pin "2") (pinfunction "2_2") (pintype "passive"))
      (node (ref "R34") (pin "2") (pinfunction "2_2") (pintype "passive"))
    )
    (net (code "49") (name "Net-(IC5B-IN-)") (class "Default")
      (node (ref "IC5") (pin "6") (pinfunction "IN-_6") (pintype "input"))
      (node (ref "R37") (pin "2") (pinfunction "2_2") (pintype "passive"))
      (node (ref "R38") (pin "1") (pinfunction "1_1") (pintype "passive"))
    )
    (net (code "50") (name "Net-(IC6A-IN+)") (class "Default")
      (node (ref "IC6") (pin "3") (pinfunction "IN+_3") (pintype "input"))
      (node (ref "R63") (pin "2") (pinfunction "2_2") (pintype "passive"))
      (node (ref "R65") (pin "2") (pinfunction "2_2") (pintype "passive"))
    )
    (net (code "51") (name "Net-(IC6A-IN-)") (class "Default")
      (node (ref "IC6") (pin "2") (pinfunction "IN-_2") (pintype "input"))
      (node (ref "R67") (pin "2") (pinfunction "2_2") (pintype "passive"))
      (node (ref "R68") (pin "1") (pinfunction "1_1") (pintype "passive"))
    )
    (net (code "52") (name "Net-(IC6B-IN+)") (class "Default")
      (node (ref "IC6") (pin "5") (pinfunction "IN+_5") (pintype "input"))
      (node (ref "R64") (pin "2") (pinfunction "2_2") (pintype "passive"))
      (node (ref "R66") (pin "2") (pinfunction "2_2") (pintype "passive"))
    )
    (net (code "53") (name "Net-(IC6B-IN-)") (class "Default")
      (node (ref "IC6") (pin "6") (pinfunction "IN-_6") (pintype "input"))
      (node (ref "R69") (pin "2") (pinfunction "2_2") (pintype "passive"))
      (node (ref "R70") (pin "1") (pinfunction "1_1") (pintype "passive"))
    )
    (net (code "54") (name "Net-(U3-+OUTPUT)") (class "Default")
      (node (ref "U3") (pin "3") (pinfunction "+OUTPUT_3") (pintype "passive"))
      (node (ref "U5") (pin "3") (pinfunction "+_3") (pintype "passive"))
    )
    (net (code "55") (name "Net-(U4-+OUTPUT)") (class "Default")
      (node (ref "U4") (pin "3") (pinfunction "+OUTPUT_3") (pintype "passive"))
      (node (ref "U6") (pin "3") (pinfunction "+_3") (pintype "passive"))
    )
    (net (code "56") (name "Net-(U5--)") (class "Default")
      (node (ref "U3") (pin "1") (pinfunction "-OUTPUT_1") (pintype "passive"))
      (node (ref "U3") (pin "6") (pinfunction "-OUTPUT_6") (pintype "passive"))
      (node (ref "U5") (pin "2") (pinfunction "-_2") (pintype "passive"))
    )
    (net (code "57") (name "Net-(U5-RG-Pad1)") (class "Default")
      (node (ref "U5") (pin "1") (pinfunction "RG_1") (pintype "passive"))
      (node (ref "VR1") (pin "1") (pinfunction "1_1") (pintype "passive"))
      (node (ref "VR1") (pin "2") (pinfunction "2_2") (pintype "passive"))
    )
    (net (code "58") (name "Net-(U5-RG-Pad8)") (class "Default")
      (node (ref "U5") (pin "8") (pinfunction "RG_8") (pintype "passive"))
      (node (ref "VR1") (pin "3") (pinfunction "3_3") (pintype "passive"))
    )
    (net (code "59") (name "Net-(U6--)") (class "Default")
      (node (ref "U4") (pin "1") (pinfunction "-OUTPUT_1") (pintype "passive"))
      (node (ref "U4") (pin "6") (pinfunction "-OUTPUT_6") (pintype "passive"))
      (node (ref "U6") (pin "2") (pinfunction "-_2") (pintype "passive"))
    )
    (net (code "60") (name "Net-(U6-RG-Pad1)") (class "Default")
      (node (ref "U6") (pin "1") (pinfunction "RG_1") (pintype "passive"))
      (node (ref "VR2") (pin "1") (pinfunction "1_1") (pintype "passive"))
      (node (ref "VR2") (pin "2") (pinfunction "2_2") (pintype "passive"))
    )
    (net (code "61") (name "Net-(U6-RG-Pad8)") (class "Default")
      (node (ref "U6") (pin "8") (pinfunction "RG_8") (pintype "passive"))
      (node (ref "VR2") (pin "3") (pinfunction "3_3") (pintype "passive"))
    )
    (net (code "62") (name "Net-(U7-IN+)") (class "Default")
      (node (ref "R14") (pin "2") (pinfunction "2_2") (pintype "passive"))
      (node (ref "R15") (pin "1") (pinfunction "1_1") (pintype "passive"))
      (node (ref "U7") (pin "3") (pinfunction "IN+_3") (pintype "input"))
    )
    (net (code "63") (name "Net-(U10-+)") (class "Default")
      (node (ref "U10") (pin "3") (pinfunction "+_3") (pintype "passive"))
      (node (ref "U8") (pin "3") (pinfunction "+OUTPUT_3") (pintype "passive"))
    )
    (net (code "64") (name "Net-(U10--)") (class "Default")
      (node (ref "U10") (pin "2") (pinfunction "-_2") (pintype "passive"))
      (node (ref "U8") (pin "1") (pinfunction "-OUTPUT_1") (pintype "passive"))
      (node (ref "U8") (pin "6") (pinfunction "-OUTPUT_6") (pintype "passive"))
    )
    (net (code "65") (name "Net-(U10-RG-Pad1)") (class "Default")
      (node (ref "U10") (pin "1") (pinfunction "RG_1") (pintype "passive"))
      (node (ref "VR3") (pin "1") (pinfunction "1_1") (pintype "passive"))
      (node (ref "VR3") (pin "2") (pinfunction "2_2") (pintype "passive"))
    )
    (net (code "66") (name "Net-(U10-RG-Pad8)") (class "Default")
      (node (ref "U10") (pin "8") (pinfunction "RG_8") (pintype "passive"))
      (node (ref "VR3") (pin "3") (pinfunction "3_3") (pintype "passive"))
    )
    (net (code "67") (name "Net-(U12-+)") (class "Default")
      (node (ref "U12") (pin "3") (pinfunction "+_3") (pintype "passive"))
      (node (ref "U9") (pin "3") (pinfunction "+OUTPUT_3") (pintype "passive"))
    )
    (net (code "68") (name "Net-(U12--)") (class "Default")
      (node (ref "U12") (pin "2") (pinfunction "-_2") (pintype "passive"))
      (node (ref "U9") (pin "1") (pinfunction "-OUTPUT_1") (pintype "passive"))
      (node (ref "U9") (pin "6") (pinfunction "-OUTPUT_6") (pintype "passive"))
    )
    (net (code "69") (name "Net-(U12-RG-Pad1)") (class "Default")
      (node (ref "U12") (pin "1") (pinfunction "RG_1") (pintype "passive"))
      (node (ref "VR4") (pin "1") (pinfunction "1_1") (pintype "passive"))
      (node (ref "VR4") (pin "2") (pinfunction "2_2") (pintype "passive"))
    )
    (net (code "70") (name "Net-(U12-RG-Pad8)") (class "Default")
      (node (ref "U12") (pin "8") (pinfunction "RG_8") (pintype "passive"))
      (node (ref "VR4") (pin "3") (pinfunction "3_3") (pintype "passive"))
    )
    (net (code "71") (name "unconnected-(U3-NC-Pad4)") (class "Default")
      (node (ref "U3") (pin "4") (pinfunction "NC_4") (pintype "passive+no_connect"))
    )
    (net (code "72") (name "unconnected-(U4-NC-Pad4)") (class "Default")
      (node (ref "U4") (pin "4") (pinfunction "NC_4") (pintype "passive+no_connect"))
    )
    (net (code "73") (name "unconnected-(U7-Vos-Pad1)") (class "Default")
      (node (ref "U7") (pin "1") (pinfunction "Vos_1") (pintype "passive"))
    )
    (net (code "74") (name "unconnected-(U7-Vos-Pad5)") (class "Default")
      (node (ref "U7") (pin "5") (pinfunction "Vos_5") (pintype "passive"))
    )
    (net (code "75") (name "unconnected-(U8-NC-Pad4)") (class "Default")
      (node (ref "U8") (pin "4") (pinfunction "NC_4") (pintype "passive+no_connect"))
    )
    (net (code "76") (name "unconnected-(U9-NC-Pad4)") (class "Default")
      (node (ref "U9") (pin "4") (pinfunction "NC_4") (pintype "passive+no_connect"))
    )
  )
)
